# shield.net
KiCad netlist of a schematic drawn in EAGLE
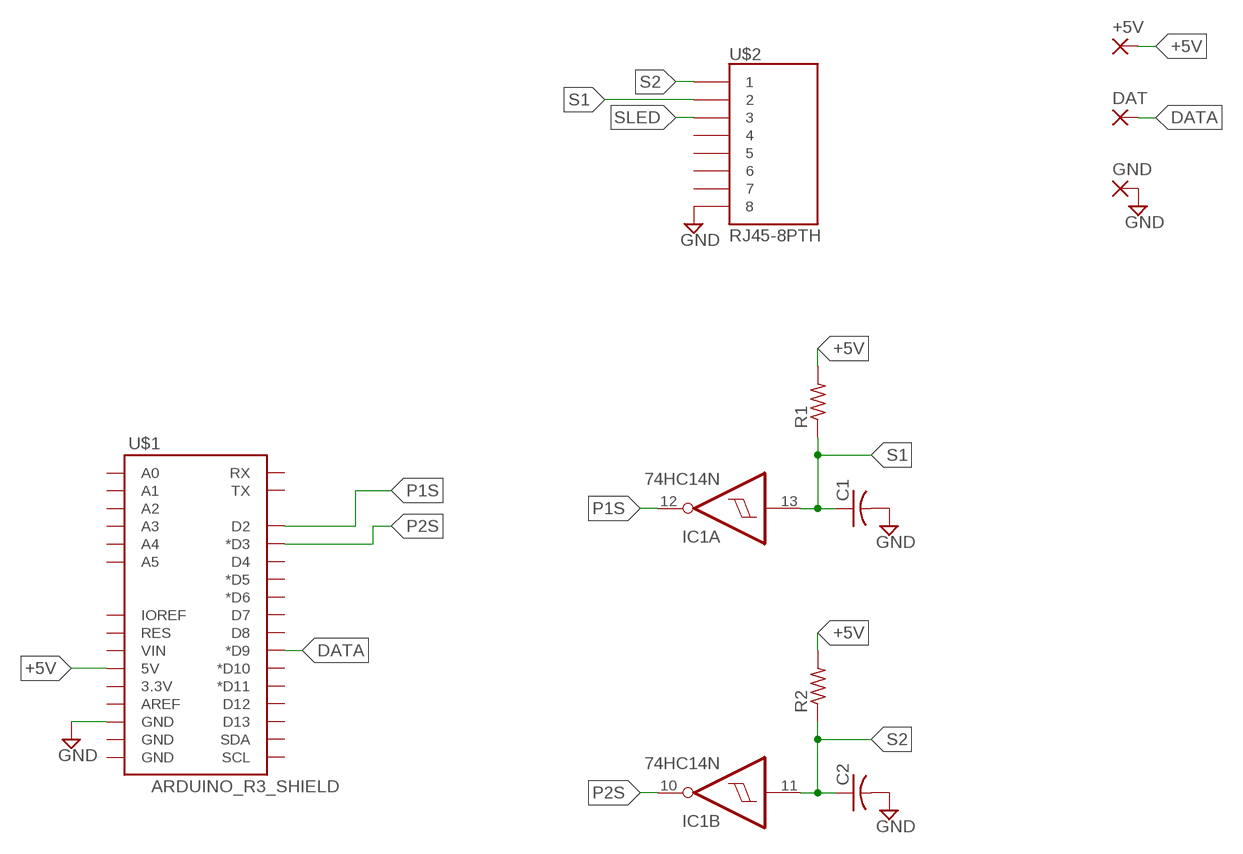
[diagram p0: schematic, sheet 1]

(export (version "E")
  (design (tool "Eeschema 10.0.6"))
  (components
    (comp (ref "+5V")
      (value "WIREPAD2,15/1,0")
      (footprint "eagle-import:2,15_1,0")
      (libsource (lib "eagle-import") (part "WIREPAD2,15/1,0"))
    )
    (comp (ref "C1")
      (value "C-US025-025X050")
      (footprint "eagle-import:C025-025X050")
      (libsource (lib "eagle-import") (part "C-US025-025X050"))
    )
    (comp (ref "C2")
      (value "C-US025-025X050")
      (footprint "eagle-import:C025-025X050")
      (libsource (lib "eagle-import") (part "C-US025-025X050"))
    )
    (comp (ref "DAT")
      (value "WIREPAD2,15/1,0")
      (footprint "eagle-import:2,15_1,0")
      (libsource (lib "eagle-import") (part "WIREPAD2,15/1,0"))
    )
    (comp (ref "GND")
      (value "WIREPAD2,15/1,0")
      (footprint "eagle-import:2,15_1,0")
      (libsource (lib "eagle-import") (part "WIREPAD2,15/1,0"))
    )
    (comp (ref "IC1")
      (value "74HC14N")
      (footprint "eagle-import:DIL14")
      (libsource (lib "eagle-import") (part "7414NHC"))
    )
    (comp (ref "R1")
      (value "R-US_0207/7")
      (footprint "eagle-import:0207_7")
      (libsource (lib "eagle-import") (part "R-US_0207/7"))
    )
    (comp (ref "R2")
      (value "R-US_0207/7")
      (footprint "eagle-import:0207_7")
      (libsource (lib "eagle-import") (part "R-US_0207/7"))
    )
    (comp (ref "U$1")
      (value "ARDUINO_R3_SHIELD")
      (footprint "eagle-import:UNO_R3_SHIELD")
      (libsource (lib "eagle-import") (part "ARDUINO_R3_SHIELD"))
    )
    (comp (ref "U$2")
      (value "RJ45-8PTH")
      (footprint "eagle-import:RJ45-8")
      (libsource (lib "eagle-import") (part "RJ45-8PTH"))
    )
  )
  (nets
    (net (code "1") (name "+5V") (class "Default")
      (node (ref "+5V") (pin "1") (pinfunction "P_1") (pintype "passive"))
      (node (ref "R1") (pin "2") (pinfunction "2_2") (pintype "passive"))
      (node (ref "R2") (pin "2") (pinfunction "2_2") (pintype "passive"))
      (node (ref "U$1") (pin "5V") (pinfunction "5V_5V") (pintype "bidirectional"))
    )
    (net (code "2") (name "DATA") (class "Default")
      (node (ref "DAT") (pin "1") (pinfunction "P_1") (pintype "passive"))
      (node (ref "U$1") (pin "D9") (pinfunction "*D9_D9") (pintype "bidirectional"))
    )
    (net (code "3") (name "GND") (class "Default")
      (node (ref "C1") (pin "2") (pinfunction "2_2") (pintype "passive"))
      (node (ref "C2") (pin "2") (pinfunction "2_2") (pintype "passive"))
      (node (ref "GND") (pin "1") (pinfunction "P_1") (pintype "passive"))
      (node (ref "U$1") (pin "GND@2") (pinfunction "GND_GND@2") (pintype "bidirectional"))
      (node (ref "U$2") (pin "8") (pinfunction "8_8") (pintype "bidirectional"))
    )
    (net (code "4") (name "P1S") (class "Default")
      (node (ref "IC1") (pin "12") (pinfunction "O_12") (pintype "output"))
      (node (ref "U$1") (pin "D2") (pinfunction "D2_D2") (pintype "bidirectional"))
    )
    (net (code "5") (name "P2S") (class "Default")
      (node (ref "IC1") (pin "10") (pinfunction "O_10") (pintype "output"))
      (node (ref "U$1") (pin "D3") (pinfunction "*D3_D3") (pintype "bidirectional"))
    )
    (net (code "6") (name "S1") (class "Default")
      (node (ref "C1") (pin "1") (pinfunction "1_1") (pintype "passive"))
      (node (ref "IC1") (pin "13") (pinfunction "I_13") (pintype "input"))
      (node (ref "R1") (pin "1") (pinfunction "1_1") (pintype "passive"))
      (node (ref "U$2") (pin "2") (pinfunction "2_2") (pintype "bidirectional"))
    )
    (net (code "7") (name "S2") (class "Default")
      (node (ref "C2") (pin "1") (pinfunction "1_1") (pintype "passive"))
      (node (ref "IC1") (pin "11") (pinfunction "I_11") (pintype "input"))
      (node (ref "R2") (pin "1") (pinfunction "1_1") (pintype "passive"))
      (node (ref "U$2") (pin "1") (pinfunction "1_1") (pintype "bidirectional"))
    )
    (net (code "8") (name "SLED") (class "Default")
      (node (ref "U$2") (pin "3") (pinfunction "3_3") (pintype "bidirectional"))
    )
    (net (code "9") (name "unconnected-(U$1-*D5-PadD5)") (class "Default")
      (node (ref "U$1") (pin "D5") (pinfunction "*D5_D5") (pintype "bidirectional"))
    )
    (net (code "10") (name "unconnected-(U$1-*D6-PadD6)") (class "Default")
      (node (ref "U$1") (pin "D6") (pinfunction "*D6_D6") (pintype "bidirectional"))
    )
    (net (code "11") (name "unconnected-(U$1-*D10-PadD10)") (class "Default")
      (node (ref "U$1") (pin "D10") (pinfunction "*D10_D10") (pintype "bidirectional"))
    )
    (net (code "12") (name "unconnected-(U$1-*D11-PadD11)") (class "Default")
      (node (ref "U$1") (pin "D11") (pinfunction "*D11_D11") (pintype "bidirectional"))
    )
    (net (code "13") (name "unconnected-(U$1-GND-PadGND@0)") (class "Default")
      (node (ref "U$1") (pin "GND@0") (pinfunction "GND_GND@0") (pintype "bidirectional"))
    )
    (net (code "14") (name "unconnected-(U$1-GND-PadGND@1)") (class "Default")
      (node (ref "U$1") (pin "GND@1") (pinfunction "GND_GND@1") (pintype "bidirectional"))
    )
    (net (code "15") (name "unconnected-(U$1-Pad3.3V)") (class "Default")
      (node (ref "U$1") (pin "3.3V") (pinfunction "3.3V_3.3V") (pintype "bidirectional"))
    )
    (net (code "16") (name "unconnected-(U$1-PadA0)") (class "Default")
      (node (ref "U$1") (pin "A0") (pinfunction "A0_A0") (pintype "bidirectional"))
    )
    (net (code "17") (name "unconnected-(U$1-PadA1)") (class "Default")
      (node (ref "U$1") (pin "A1") (pinfunction "A1_A1") (pintype "bidirectional"))
    )
    (net (code "18") (name "unconnected-(U$1-PadA2)") (class "Default")
      (node (ref "U$1") (pin "A2") (pinfunction "A2_A2") (pintype "bidirectional"))
    )
    (net (code "19") (name "unconnected-(U$1-PadA3)") (class "Default")
      (node (ref "U$1") (pin "A3") (pinfunction "A3_A3") (pintype "bidirectional"))
    )
    (net (code "20") (name "unconnected-(U$1-PadA4)") (class "Default")
      (node (ref "U$1") (pin "A4") (pinfunction "A4_A4") (pintype "bidirectional"))
    )
    (net (code "21") (name "unconnected-(U$1-PadA5)") (class "Default")
      (node (ref "U$1") (pin "A5") (pinfunction "A5_A5") (pintype "bidirectional"))
    )
    (net (code "22") (name "unconnected-(U$1-PadAREF)") (class "Default")
      (node (ref "U$1") (pin "AREF") (pinfunction "AREF_AREF") (pintype "bidirectional"))
    )
    (net (code "23") (name "unconnected-(U$1-PadD4)") (class "Default")
      (node (ref "U$1") (pin "D4") (pinfunction "D4_D4") (pintype "bidirectional"))
    )
    (net (code "24") (name "unconnected-(U$1-PadD7)") (class "Default")
      (node (ref "U$1") (pin "D7") (pinfunction "D7_D7") (pintype "bidirectional"))
    )
    (net (code "25") (name "unconnected-(U$1-PadD8)") (class "Default")
      (node (ref "U$1") (pin "D8") (pinfunction "D8_D8") (pintype "bidirectional"))
    )
    (net (code "26") (name "unconnected-(U$1-PadD12)") (class "Default")
      (node (ref "U$1") (pin "D12") (pinfunction "D12_D12") (pintype "bidirectional"))
    )
    (net (code "27") (name "unconnected-(U$1-PadD13)") (class "Default")
      (node (ref "U$1") (pin "D13") (pinfunction "D13_D13") (pintype "bidirectional"))
    )
    (net (code "28") (name "unconnected-(U$1-PadIOREF)") (class "Default")
      (node (ref "U$1") (pin "IOREF") (pinfunction "IOREF_IOREF") (pintype "bidirectional"))
    )
    (net (code "29") (name "unconnected-(U$1-PadRES)") (class "Default")
      (node (ref "U$1") (pin "RES") (pinfunction "RES_RES") (pintype "bidirectional"))
    )
    (net (code "30") (name "unconnected-(U$1-PadRX)") (class "Default")
      (node (ref "U$1") (pin "RX") (pinfunction "RX_RX") (pintype "bidirectional"))
    )
    (net (code "31") (name "unconnected-(U$1-PadSCL)") (class "Default")
      (node (ref "U$1") (pin "SCL") (pinfunction "SCL_SCL") (pintype "bidirectional"))
    )
    (net (code "32") (name "unconnected-(U$1-PadSDA)") (class "Default")
      (node (ref "U$1") (pin "SDA") (pinfunction "SDA_SDA") (pintype "bidirectional"))
    )
    (net (code "33") (name "unconnected-(U$1-PadTX)") (class "Default")
      (node (ref "U$1") (pin "TX") (pinfunction "TX_TX") (pintype "bidirectional"))
    )
    (net (code "34") (name "unconnected-(U$1-PadVIN)") (class "Default")
      (node (ref "U$1") (pin "VIN") (pinfunction "VIN_VIN") (pintype "bidirectional"))
    )
    (net (code "35") (name "unconnected-(U$2-Pad4)") (class "Default")
      (node (ref "U$2") (pin "4") (pinfunction "4_4") (pintype "bidirectional"))
    )
    (net (code "36") (name "unconnected-(U$2-Pad5)") (class "Default")
      (node (ref "U$2") (pin "5") (pinfunction "5_5") (pintype "bidirectional"))
    )
    (net (code "37") (name "unconnected-(U$2-Pad6)") (class "Default")
      (node (ref "U$2") (pin "6") (pinfunction "6_6") (pintype "bidirectional"))
    )
    (net (code "38") (name "unconnected-(U$2-Pad7)") (class "Default")
      (node (ref "U$2") (pin "7") (pinfunction "7_7") (pintype "bidirectional"))
    )
  )
)
